# Sheet2_W5500_1.net
KiCad netlist of a schematic drawn in Altium Designer
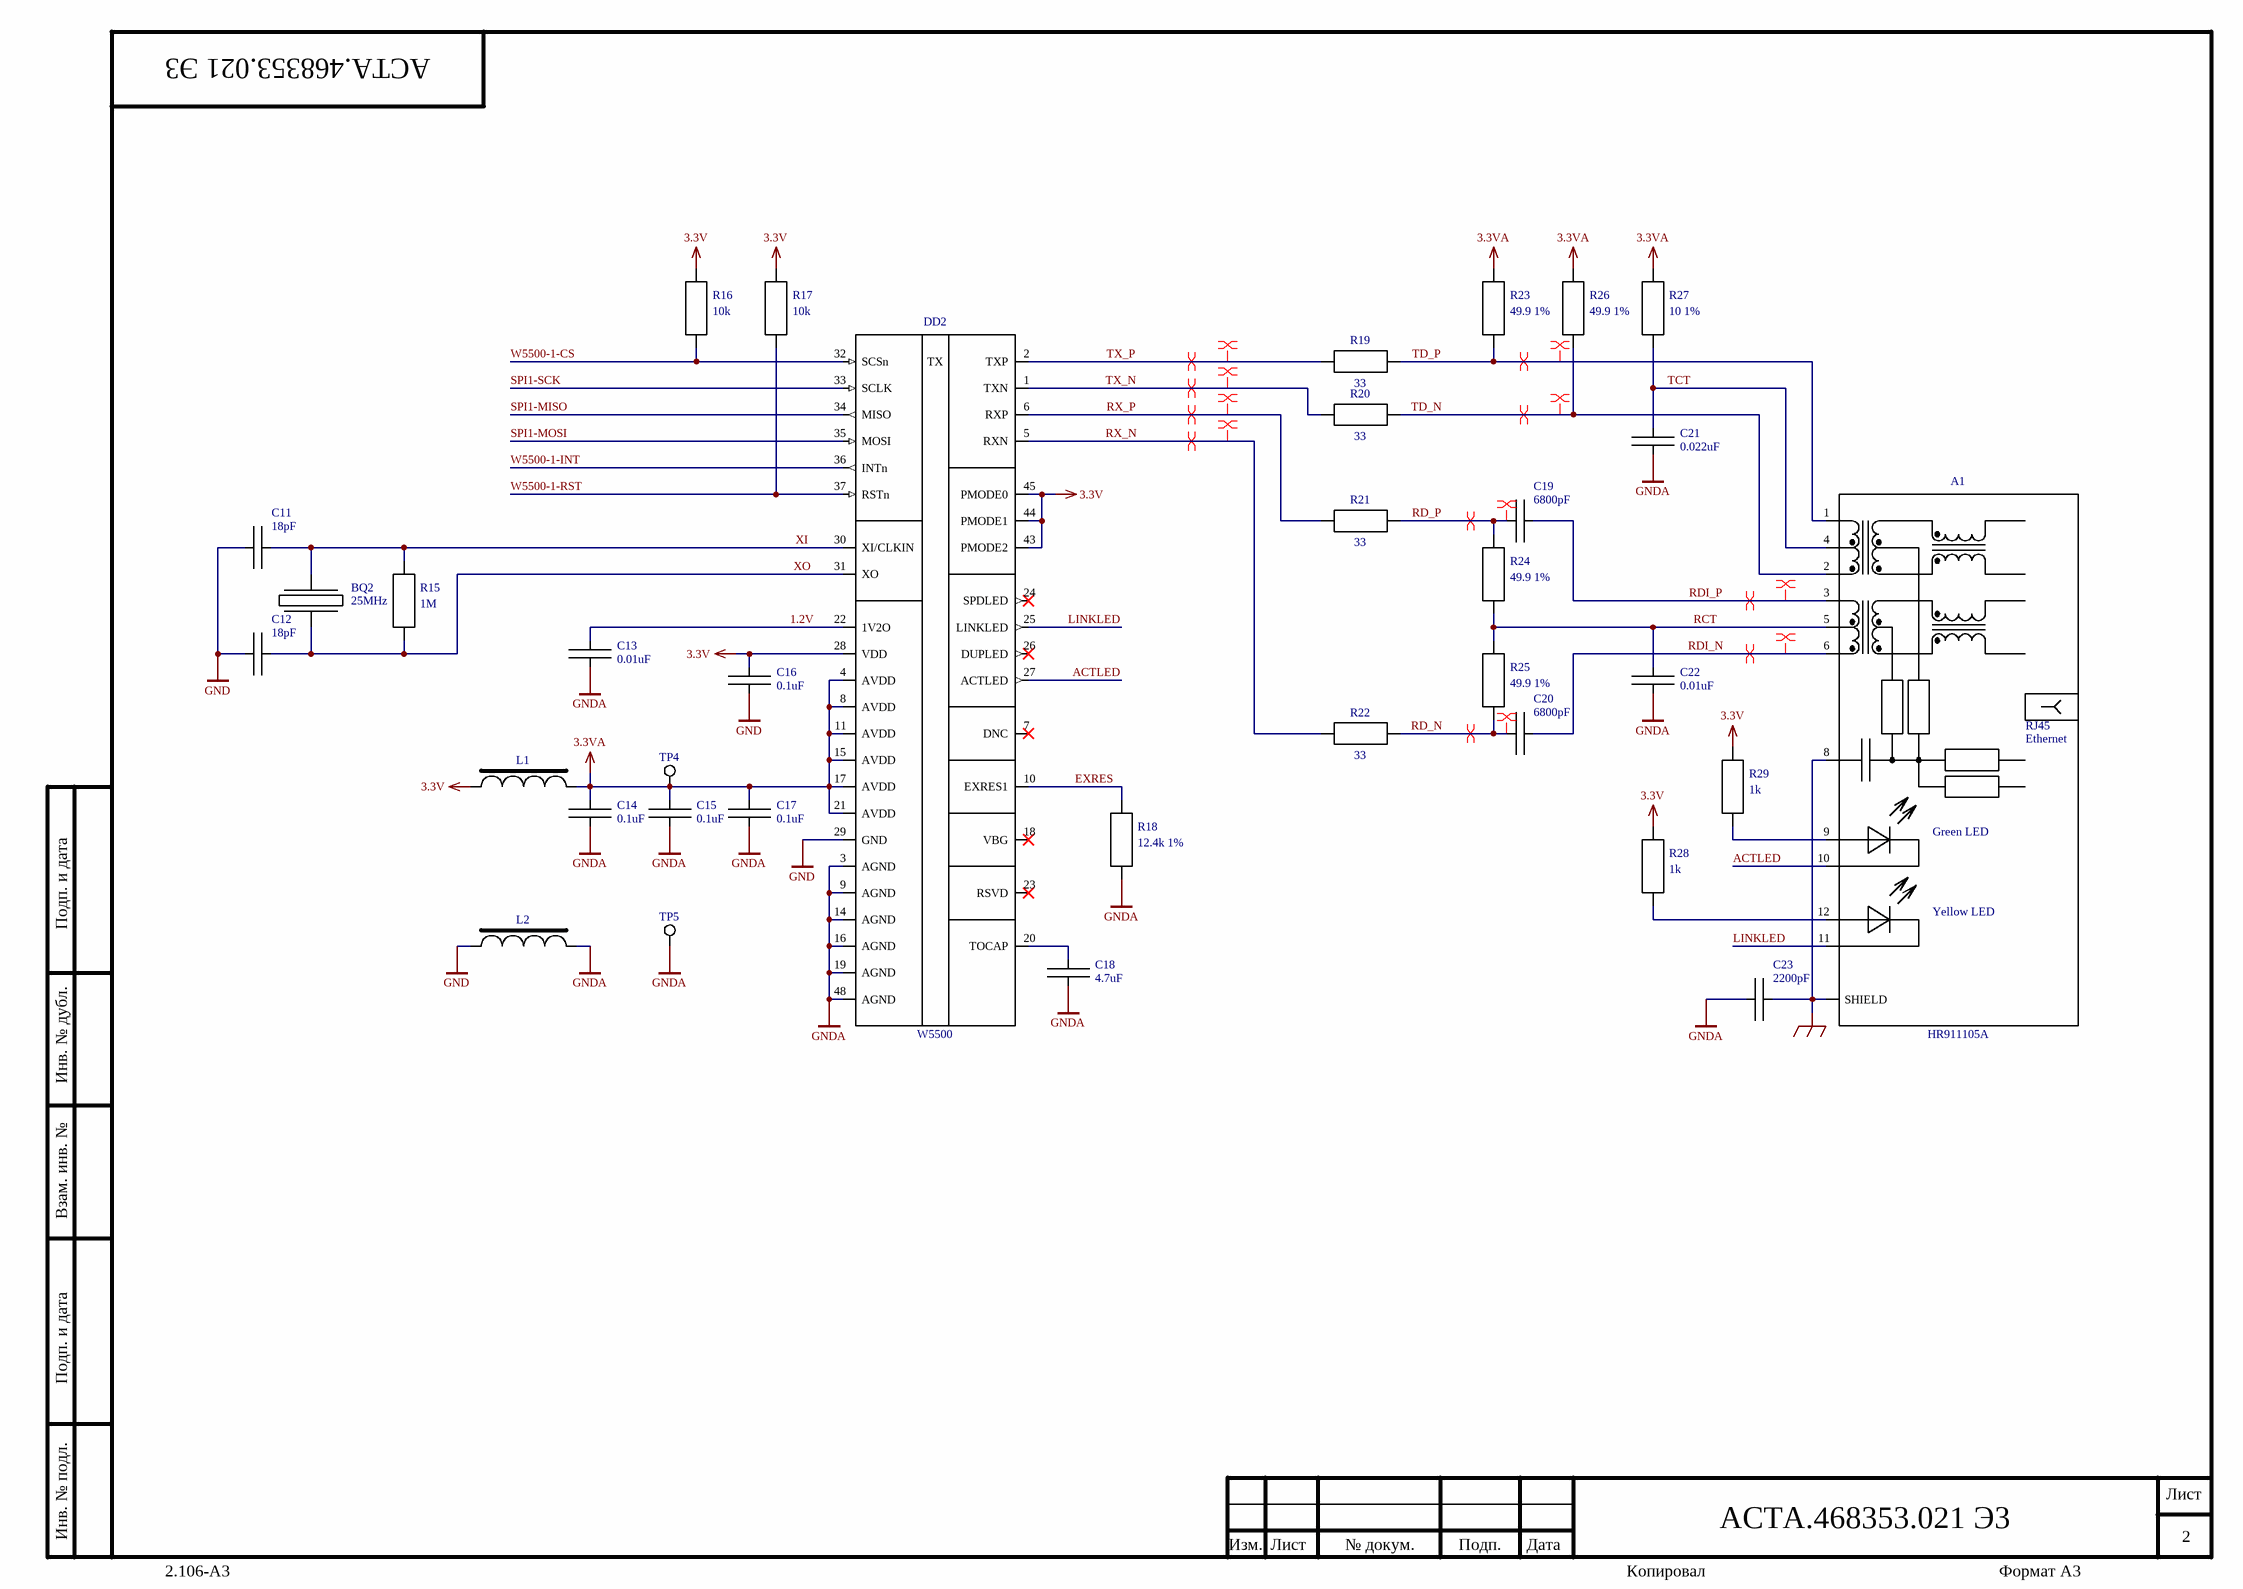
[diagram p0: Sheet2_W5500_1.SchDoc]

(export (version "E")
  (design (tool "Eeschema 10.0.6"))
  (components
    (comp (ref "A1")
      (value "HR911105A")
      (footprint "HR911105A")
      (description "Ethernet Connector 10/100 1x1 Tab Down RJ45 w/mag G/Y LED")
      (libsource (lib "Devices") (part "HR911105A"))
    )
    (comp (ref "BQ2")
      (value "25MHz")
      (footprint "HT-49S")
      (fields (field (name "Comment") "HT-49S_Rated"))
      (libsource (lib "Resonators") (part "HT-49S_Rated"))
    )
    (comp (ref "C11")
      (value "18pF")
      (footprint "CAP0805")
      (fields (field (name "Comment") "CAP0805_Rated"))
      (libsource (lib "Ceramic_Capacitors") (part "CAP0805_Rated"))
    )
    (comp (ref "C12")
      (value "18pF")
      (footprint "CAP0805")
      (fields (field (name "Comment") "CAP0805_Rated"))
      (libsource (lib "Ceramic_Capacitors") (part "CAP0805_Rated"))
    )
    (comp (ref "C13")
      (value "0.01uF")
      (footprint "CAP0805")
      (fields (field (name "Comment") "CAP0805_Rated"))
      (libsource (lib "Ceramic_Capacitors") (part "CAP0805_Rated"))
    )
    (comp (ref "C14")
      (value "0.1uF")
      (footprint "CAP0805")
      (fields (field (name "Comment") "CAP0805_Rated"))
      (libsource (lib "Ceramic_Capacitors") (part "CAP0805_Rated"))
    )
    (comp (ref "C15")
      (value "0.1uF")
      (footprint "CAP0805")
      (fields (field (name "Comment") "CAP0805_Rated"))
      (libsource (lib "Ceramic_Capacitors") (part "CAP0805_Rated"))
    )
    (comp (ref "C16")
      (value "0.1uF")
      (footprint "CAP0805")
      (fields (field (name "Comment") "CAP0805_Rated"))
      (libsource (lib "Ceramic_Capacitors") (part "CAP0805_Rated"))
    )
    (comp (ref "C17")
      (value "0.1uF")
      (footprint "CAP0805")
      (fields (field (name "Comment") "CAP0805_Rated"))
      (libsource (lib "Ceramic_Capacitors") (part "CAP0805_Rated"))
    )
    (comp (ref "C18")
      (value "4.7uF")
      (footprint "CAP1206")
      (fields (field (name "Comment") "CAP1206_Rated"))
      (libsource (lib "Ceramic_Capacitors") (part "CAP1206_Rated"))
    )
    (comp (ref "C19")
      (value "6800pF")
      (footprint "CAP0805")
      (fields (field (name "Comment") "CAP0805_Rated"))
      (libsource (lib "Ceramic_Capacitors") (part "CAP0805_Rated"))
    )
    (comp (ref "C20")
      (value "6800pF")
      (footprint "CAP0805")
      (fields (field (name "Comment") "CAP0805_Rated"))
      (libsource (lib "Ceramic_Capacitors") (part "CAP0805_Rated"))
    )
    (comp (ref "C21")
      (value "0.022uF")
      (footprint "CAP0805")
      (fields (field (name "Comment") "CAP0805_Rated"))
      (libsource (lib "Ceramic_Capacitors") (part "CAP0805_Rated"))
    )
    (comp (ref "C22")
      (value "0.01uF")
      (footprint "CAP0805")
      (fields (field (name "Comment") "CAP0805_Rated"))
      (libsource (lib "Ceramic_Capacitors") (part "CAP0805_Rated"))
    )
    (comp (ref "C23")
      (value "2200pF")
      (footprint "CAP1812")
      (fields (field (name "Comment") "CAP1812_Rated"))
      (libsource (lib "Ceramic_Capacitors") (part "CAP1812_Rated"))
    )
    (comp (ref "DD2")
      (value "W5500")
      (footprint "LQFP-48")
      (description "Ethernet ICs 3in1 Enet Controller TCP/IP +MAC+PHY")
      (libsource (lib "Interface_ICs") (part "W5500"))
    )
    (comp (ref "L1")
      (value "BLM21BD121SN1D")
      (footprint "IND0805")
      (description "Ferrite Bead 0805 120 Ohm")
      (fields (field (name "MANUFACTURER") "Murata") (field (name "TOLERANCE") "25%"))
      (libsource (lib "Inductors") (part "BLM21BD121SN1D"))
    )
    (comp (ref "L2")
      (value "BLM21BD121SN1D")
      (footprint "IND0805")
      (description "Ferrite Bead 0805 120 Ohm")
      (fields (field (name "MANUFACTURER") "Murata") (field (name "TOLERANCE") "25%"))
      (libsource (lib "Inductors") (part "BLM21BD121SN1D"))
    )
    (comp (ref "R15")
      (value "1M")
      (footprint "RES0805")
      (fields (field (name "TOLERANCE") "5%") (field (name "Comment") "RES0805_Rated"))
      (libsource (lib "Resistors") (part "RES0805_Rated"))
    )
    (comp (ref "R16")
      (value "10k")
      (footprint "RES0805")
      (fields (field (name "TOLERANCE") "5%") (field (name "Comment") "RES0805_Rated"))
      (libsource (lib "Resistors") (part "RES0805_Rated"))
    )
    (comp (ref "R17")
      (value "10k")
      (footprint "RES0805")
      (fields (field (name "TOLERANCE") "5%") (field (name "Comment") "RES0805_Rated"))
      (libsource (lib "Resistors") (part "RES0805_Rated"))
    )
    (comp (ref "R18")
      (value "12.4k 1%")
      (footprint "RES0805")
      (fields (field (name "TOLERANCE") "5%") (field (name "Comment") "RES0805_Rated"))
      (libsource (lib "Resistors") (part "RES0805_Rated"))
    )
    (comp (ref "R19")
      (value "33")
      (footprint "RES0805")
      (fields (field (name "TOLERANCE") "5%") (field (name "Comment") "RES0805_Rated"))
      (libsource (lib "") (part "RES0805_Rated_1"))
    )
    (comp (ref "R20")
      (value "33")
      (footprint "RES0805")
      (fields (field (name "TOLERANCE") "5%") (field (name "Comment") "RES0805_Rated"))
      (libsource (lib "") (part "RES0805_Rated_1"))
    )
    (comp (ref "R21")
      (value "33")
      (footprint "RES0805")
      (fields (field (name "TOLERANCE") "5%") (field (name "Comment") "RES0805_Rated"))
      (libsource (lib "") (part "RES0805_Rated_1"))
    )
    (comp (ref "R22")
      (value "33")
      (footprint "RES0805")
      (fields (field (name "TOLERANCE") "5%") (field (name "Comment") "RES0805_Rated"))
      (libsource (lib "") (part "RES0805_Rated_1"))
    )
    (comp (ref "R23")
      (value "49.9 1%")
      (footprint "RES0805")
      (fields (field (name "TOLERANCE") "5%") (field (name "Comment") "RES0805_Rated"))
      (libsource (lib "Resistors") (part "RES0805_Rated"))
    )
    (comp (ref "R24")
      (value "49.9 1%")
      (footprint "RES0805")
      (fields (field (name "TOLERANCE") "5%") (field (name "Comment") "RES0805_Rated"))
      (libsource (lib "Resistors") (part "RES0805_Rated"))
    )
    (comp (ref "R25")
      (value "49.9 1%")
      (footprint "RES0805")
      (fields (field (name "TOLERANCE") "5%") (field (name "Comment") "RES0805_Rated"))
      (libsource (lib "Resistors") (part "RES0805_Rated"))
    )
    (comp (ref "R26")
      (value "49.9 1%")
      (footprint "RES0805")
      (fields (field (name "TOLERANCE") "5%") (field (name "Comment") "RES0805_Rated"))
      (libsource (lib "Resistors") (part "RES0805_Rated"))
    )
    (comp (ref "R27")
      (value "10 1%")
      (footprint "RES0805")
      (fields (field (name "TOLERANCE") "5%") (field (name "Comment") "RES0805_Rated"))
      (libsource (lib "Resistors") (part "RES0805_Rated"))
    )
    (comp (ref "R28")
      (value "1k")
      (footprint "RES0805")
      (fields (field (name "TOLERANCE") "5%") (field (name "Comment") "RES0805_Rated"))
      (libsource (lib "Resistors") (part "RES0805_Rated"))
    )
    (comp (ref "R29")
      (value "1k")
      (footprint "RES0805")
      (fields (field (name "TOLERANCE") "5%") (field (name "Comment") "RES0805_Rated"))
      (libsource (lib "Resistors") (part "RES0805_Rated"))
    )
    (comp (ref "TP4")
      (value "TestPad")
      (footprint "PAD-TH-OCT1x1-0.5")
      (description "TestPoint on PCB")
      (libsource (lib "Connectors") (part "TestPad"))
    )
    (comp (ref "TP5")
      (value "TestPad")
      (footprint "PAD-TH-OCT1x1-0.5")
      (description "TestPoint on PCB")
      (libsource (lib "Connectors") (part "TestPad"))
    )
  )
  (nets
    (net (code "1") (name "/1.2V") (class "Default")
      (node (ref "C13") (pin "1") (pinfunction "1_1") (pintype "passive"))
      (node (ref "DD2") (pin "22") (pinfunction "1V2O_22") (pintype "power_in"))
    )
    (net (code "2") (name "/ACTLED") (class "Default")
      (node (ref "A1") (pin "10") (pinfunction "LED1-K_10") (pintype "passive"))
      (node (ref "DD2") (pin "27") (pinfunction "ACTLED_27") (pintype "output"))
    )
    (net (code "3") (name "/EXRES") (class "Default")
      (node (ref "DD2") (pin "10") (pinfunction "EXRES1_10") (pintype "passive"))
      (node (ref "R18") (pin "2") (pinfunction "2_2") (pintype "passive"))
    )
    (net (code "4") (name "/LINKLED") (class "Default")
      (node (ref "A1") (pin "11") (pinfunction "LED2-A_11") (pintype "passive"))
      (node (ref "DD2") (pin "25") (pinfunction "LINKLED_25") (pintype "output"))
    )
    (net (code "5") (name "/RCT") (class "Default")
      (node (ref "A1") (pin "5") (pinfunction "CT_5") (pintype "passive"))
      (node (ref "C22") (pin "1") (pinfunction "1_1") (pintype "passive"))
      (node (ref "R24") (pin "1") (pinfunction "1_1") (pintype "passive"))
      (node (ref "R25") (pin "2") (pinfunction "2_2") (pintype "passive"))
    )
    (net (code "6") (name "/RDI_N") (class "Default")
      (node (ref "A1") (pin "6") (pinfunction "RD-_6") (pintype "passive"))
      (node (ref "C20") (pin "2") (pinfunction "2_2") (pintype "passive"))
    )
    (net (code "7") (name "/RDI_P") (class "Default")
      (node (ref "A1") (pin "3") (pinfunction "RD+_3") (pintype "passive"))
      (node (ref "C19") (pin "2") (pinfunction "2_2") (pintype "passive"))
    )
    (net (code "8") (name "/RD_N") (class "Default")
      (node (ref "C20") (pin "1") (pinfunction "1_1") (pintype "passive"))
      (node (ref "R22") (pin "2") (pinfunction "2_2") (pintype "passive"))
      (node (ref "R25") (pin "1") (pinfunction "1_1") (pintype "passive"))
    )
    (net (code "9") (name "/RD_P") (class "Default")
      (node (ref "C19") (pin "1") (pinfunction "1_1") (pintype "passive"))
      (node (ref "R21") (pin "2") (pinfunction "2_2") (pintype "passive"))
      (node (ref "R24") (pin "2") (pinfunction "2_2") (pintype "passive"))
    )
    (net (code "10") (name "/RX_N") (class "Default")
      (node (ref "DD2") (pin "5") (pinfunction "RXN_5") (pintype "passive"))
      (node (ref "R22") (pin "1") (pinfunction "1_1") (pintype "passive"))
    )
    (net (code "11") (name "/RX_P") (class "Default")
      (node (ref "DD2") (pin "6") (pinfunction "RXP_6") (pintype "passive"))
      (node (ref "R21") (pin "1") (pinfunction "1_1") (pintype "passive"))
    )
    (net (code "12") (name "/SPI1-MISO") (class "Default")
      (node (ref "DD2") (pin "34") (pinfunction "MISO_34") (pintype "output"))
    )
    (net (code "13") (name "/SPI1-MOSI") (class "Default")
      (node (ref "DD2") (pin "35") (pinfunction "MOSI_35") (pintype "input"))
    )
    (net (code "14") (name "/SPI1-SCK") (class "Default")
      (node (ref "DD2") (pin "33") (pinfunction "SCLK_33") (pintype "input"))
    )
    (net (code "15") (name "/TCT") (class "Default")
      (node (ref "A1") (pin "4") (pinfunction "CT_4") (pintype "passive"))
      (node (ref "C21") (pin "1") (pinfunction "1_1") (pintype "passive"))
      (node (ref "R27") (pin "1") (pinfunction "1_1") (pintype "passive"))
    )
    (net (code "16") (name "/TD_N") (class "Default")
      (node (ref "A1") (pin "2") (pinfunction "TD-_2") (pintype "passive"))
      (node (ref "R20") (pin "2") (pinfunction "2_2") (pintype "passive"))
      (node (ref "R26") (pin "1") (pinfunction "1_1") (pintype "passive"))
    )
    (net (code "17") (name "/TD_P") (class "Default")
      (node (ref "A1") (pin "1") (pinfunction "TD+_1") (pintype "passive"))
      (node (ref "R19") (pin "2") (pinfunction "2_2") (pintype "passive"))
      (node (ref "R23") (pin "1") (pinfunction "1_1") (pintype "passive"))
    )
    (net (code "18") (name "/TX_N") (class "Default")
      (node (ref "DD2") (pin "1") (pinfunction "TXN_1") (pintype "passive"))
      (node (ref "R20") (pin "1") (pinfunction "1_1") (pintype "passive"))
    )
    (net (code "19") (name "/TX_P") (class "Default")
      (node (ref "DD2") (pin "2") (pinfunction "TXP_2") (pintype "passive"))
      (node (ref "R19") (pin "1") (pinfunction "1_1") (pintype "passive"))
    )
    (net (code "20") (name "/W5500-1-CS") (class "Default")
      (node (ref "DD2") (pin "32") (pinfunction "SCSn_32") (pintype "input"))
      (node (ref "R16") (pin "1") (pinfunction "1_1") (pintype "passive"))
    )
    (net (code "21") (name "/W5500-1-INT") (class "Default")
      (node (ref "DD2") (pin "36") (pinfunction "INTn_36") (pintype "output"))
    )
    (net (code "22") (name "/W5500-1-RST") (class "Default")
      (node (ref "DD2") (pin "37") (pinfunction "RSTn_37") (pintype "input"))
      (node (ref "R17") (pin "1") (pinfunction "1_1") (pintype "passive"))
    )
    (net (code "23") (name "/XI") (class "Default")
      (node (ref "BQ2") (pin "1") (pinfunction "1_1") (pintype "passive"))
      (node (ref "C11") (pin "2") (pinfunction "2_2") (pintype "passive"))
      (node (ref "DD2") (pin "30") (pinfunction "XI/CLKIN_30") (pintype "passive"))
      (node (ref "R15") (pin "2") (pinfunction "2_2") (pintype "passive"))
    )
    (net (code "24") (name "/XO") (class "Default")
      (node (ref "BQ2") (pin "2") (pinfunction "2_2") (pintype "passive"))
      (node (ref "C12") (pin "2") (pinfunction "2_2") (pintype "passive"))
      (node (ref "DD2") (pin "31") (pinfunction "XO_31") (pintype "passive"))
      (node (ref "R15") (pin "1") (pinfunction "1_1") (pintype "passive"))
    )
    (net (code "25") (name "3.3V") (class "Default")
      (node (ref "C16") (pin "1") (pinfunction "1_1") (pintype "passive"))
      (node (ref "DD2") (pin "28") (pinfunction "VDD_28") (pintype "power_in"))
      (node (ref "DD2") (pin "43") (pinfunction "PMODE2_43") (pintype "passive"))
      (node (ref "DD2") (pin "44") (pinfunction "PMODE1_44") (pintype "passive"))
      (node (ref "DD2") (pin "45") (pinfunction "PMODE0_45") (pintype "passive"))
      (node (ref "L1") (pin "1") (pinfunction "1_1") (pintype "passive"))
      (node (ref "R16") (pin "2") (pinfunction "2_2") (pintype "passive"))
      (node (ref "R17") (pin "2") (pinfunction "2_2") (pintype "passive"))
      (node (ref "R28") (pin "2") (pinfunction "2_2") (pintype "passive"))
      (node (ref "R29") (pin "2") (pinfunction "2_2") (pintype "passive"))
    )
    (net (code "26") (name "3.3VA") (class "Default")
      (node (ref "C14") (pin "1") (pinfunction "1_1") (pintype "passive"))
      (node (ref "C15") (pin "1") (pinfunction "1_1") (pintype "passive"))
      (node (ref "C17") (pin "1") (pinfunction "1_1") (pintype "passive"))
      (node (ref "DD2") (pin "11") (pinfunction "AVDD_11") (pintype "power_in"))
      (node (ref "DD2") (pin "15") (pinfunction "AVDD_15") (pintype "power_in"))
      (node (ref "DD2") (pin "17") (pinfunction "AVDD_17") (pintype "power_in"))
      (node (ref "DD2") (pin "21") (pinfunction "AVDD_21") (pintype "power_in"))
      (node (ref "DD2") (pin "4") (pinfunction "AVDD_4") (pintype "power_in"))
      (node (ref "DD2") (pin "8") (pinfunction "AVDD_8") (pintype "power_in"))
      (node (ref "L1") (pin "2") (pinfunction "2_2") (pintype "passive"))
      (node (ref "R23") (pin "2") (pinfunction "2_2") (pintype "passive"))
      (node (ref "R26") (pin "2") (pinfunction "2_2") (pintype "passive"))
      (node (ref "R27") (pin "2") (pinfunction "2_2") (pintype "passive"))
      (node (ref "TP4") (pin "1") (pinfunction "1_1") (pintype "passive"))
    )
    (net (code "27") (name "EARTH") (class "Default")
      (node (ref "A1") (pin "8") (pinfunction "GND_8") (pintype "power_in"))
      (node (ref "A1") (pin "SHIELD") (pinfunction "SHIELD_SHIELD") (pintype "passive"))
      (node (ref "C23") (pin "2") (pinfunction "2_2") (pintype "passive"))
    )
    (net (code "28") (name "GND") (class "Default")
      (node (ref "C11") (pin "1") (pinfunction "1_1") (pintype "passive"))
      (node (ref "C12") (pin "1") (pinfunction "1_1") (pintype "passive"))
      (node (ref "C16") (pin "2") (pinfunction "2_2") (pintype "passive"))
      (node (ref "DD2") (pin "29") (pinfunction "GND_29") (pintype "power_in"))
      (node (ref "L2") (pin "1") (pinfunction "1_1") (pintype "passive"))
    )
    (net (code "29") (name "GNDA") (class "Default")
      (node (ref "C13") (pin "2") (pinfunction "2_2") (pintype "passive"))
      (node (ref "C14") (pin "2") (pinfunction "2_2") (pintype "passive"))
      (node (ref "C15") (pin "2") (pinfunction "2_2") (pintype "passive"))
      (node (ref "C17") (pin "2") (pinfunction "2_2") (pintype "passive"))
      (node (ref "C18") (pin "2") (pinfunction "2_2") (pintype "passive"))
      (node (ref "C21") (pin "2") (pinfunction "2_2") (pintype "passive"))
      (node (ref "C22") (pin "2") (pinfunction "2_2") (pintype "passive"))
      (node (ref "C23") (pin "1") (pinfunction "1_1") (pintype "passive"))
      (node (ref "DD2") (pin "14") (pinfunction "AGND_14") (pintype "power_in"))
      (node (ref "DD2") (pin "16") (pinfunction "AGND_16") (pintype "power_in"))
      (node (ref "DD2") (pin "19") (pinfunction "AGND_19") (pintype "power_in"))
      (node (ref "DD2") (pin "3") (pinfunction "AGND_3") (pintype "power_in"))
      (node (ref "DD2") (pin "48") (pinfunction "AGND_48") (pintype "power_in"))
      (node (ref "DD2") (pin "9") (pinfunction "AGND_9") (pintype "power_in"))
      (node (ref "L2") (pin "2") (pinfunction "2_2") (pintype "passive"))
      (node (ref "R18") (pin "1") (pinfunction "1_1") (pintype "passive"))
      (node (ref "TP5") (pin "1") (pinfunction "1_1") (pintype "passive"))
    )
    (net (code "30") (name "Net-(A1-LED1-A)") (class "Default")
      (node (ref "A1") (pin "9") (pinfunction "LED1-A_9") (pintype "passive"))
      (node (ref "R29") (pin "1") (pinfunction "1_1") (pintype "passive"))
    )
    (net (code "31") (name "Net-(A1-LED2-K)") (class "Default")
      (node (ref "A1") (pin "12") (pinfunction "LED2-K_12") (pintype "passive"))
      (node (ref "R28") (pin "1") (pinfunction "1_1") (pintype "passive"))
    )
    (net (code "32") (name "Net-(DD2-TOCAP)") (class "Default")
      (node (ref "C18") (pin "1") (pinfunction "1_1") (pintype "passive"))
      (node (ref "DD2") (pin "20") (pinfunction "TOCAP_20") (pintype "passive"))
    )
    (net (code "33") (name "unconnected-(DD2-DNC-Pad7)") (class "Default")
      (node (ref "DD2") (pin "7") (pinfunction "DNC_7") (pintype "passive+no_connect"))
    )
    (net (code "34") (name "unconnected-(DD2-DUPLED-Pad26)") (class "Default")
      (node (ref "DD2") (pin "26") (pinfunction "DUPLED_26") (pintype "output+no_connect"))
    )
    (net (code "35") (name "unconnected-(DD2-RSVD-Pad23)") (class "Default")
      (node (ref "DD2") (pin "23") (pinfunction "RSVD_23") (pintype "passive+no_connect"))
    )
    (net (code "36") (name "unconnected-(DD2-SPDLED-Pad24)") (class "Default")
      (node (ref "DD2") (pin "24") (pinfunction "SPDLED_24") (pintype "output+no_connect"))
    )
    (net (code "37") (name "unconnected-(DD2-VBG-Pad18)") (class "Default")
      (node (ref "DD2") (pin "18") (pinfunction "VBG_18") (pintype "passive+no_connect"))
    )
  )
)
